# PCIe.net
KiCad netlist of a schematic drawn in Altium Designer
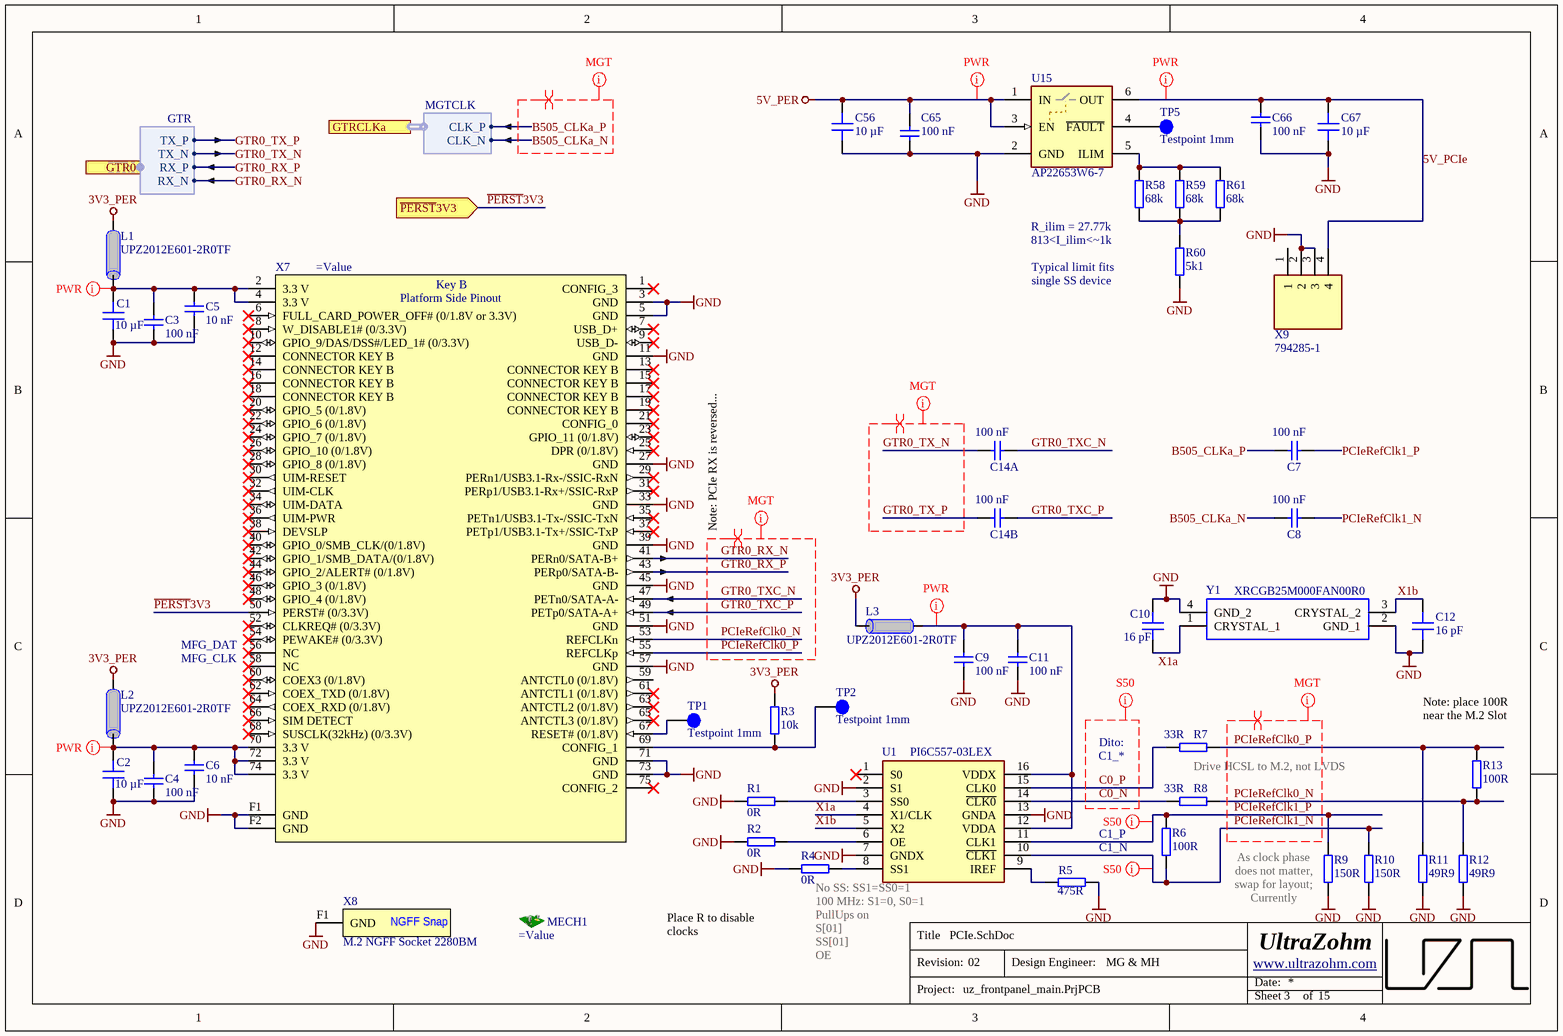
[diagram p0: PCIe.SchDoc]

(export (version "E")
  (design (tool "Eeschema 10.0.6"))
  (components
    (comp (ref "C1")
      (value "10 µF")
      (footprint "C_0603_TE")
      (description "Capacitor 0603, 16 VDC, 10 µF, X5R")
      (fields
        (field (name "MANUFACTURER PART NUMBER") "CL10A106MO8NQNC")
        (field (name "MANUFACTURER") "Samsung Electro-Mechanics")
        (field (name "CREATED FROM") "AGeiger")
      )
      (libsource (lib "user") (part "Capacitor"))
    )
    (comp (ref "C2")
      (value "10 µF")
      (footprint "C_0603_TE")
      (description "Capacitor 0603, 16 VDC, 10 µF, X5R")
      (fields
        (field (name "MANUFACTURER PART NUMBER") "CL10A106MO8NQNC")
        (field (name "MANUFACTURER") "Samsung Electro-Mechanics")
        (field (name "CREATED FROM") "AGeiger")
      )
      (libsource (lib "user") (part "Capacitor"))
    )
    (comp (ref "C3")
      (value "100 nF")
      (footprint "C_0603_TE")
      (description "Generic capacitor")
      (fields
        (field (name "MANUFACTURER PART NUMBER") "UZgen_C_0603_100nF_50V_X7R")
        (field (name "MANUFACTURER") "UZgen")
        (field (name "CREATED FROM") "AGeiger")
      )
      (libsource (lib "user") (part "CAP-NP"))
    )
    (comp (ref "C4")
      (value "100 nF")
      (footprint "C_0603_TE")
      (description "Generic capacitor")
      (fields
        (field (name "MANUFACTURER PART NUMBER") "UZgen_C_0603_100nF_50V_X7R")
        (field (name "MANUFACTURER") "UZgen")
        (field (name "CREATED FROM") "AGeiger")
      )
      (libsource (lib "user") (part "CAP-NP"))
    )
    (comp (ref "C5")
      (value "10 nF")
      (footprint "C_0603_TE")
      (description "Generic capacitor")
      (fields
        (field (name "MANUFACTURER PART NUMBER") "UZgen_C_0603_10nF_50V_X7R")
        (field (name "MANUFACTURER") "UZgen")
        (field (name "CREATED FROM") "UZgenTool")
      )
      (libsource (lib "user") (part "CAP-NP"))
    )
    (comp (ref "C6")
      (value "10 nF")
      (footprint "C_0603_TE")
      (description "Generic capacitor")
      (fields
        (field (name "MANUFACTURER PART NUMBER") "UZgen_C_0603_10nF_50V_X7R")
        (field (name "MANUFACTURER") "UZgen")
        (field (name "CREATED FROM") "UZgenTool")
      )
      (libsource (lib "user") (part "CAP-NP"))
    )
    (comp (ref "C7")
      (value "100 nF")
      (footprint "C_0402_TE")
      (description "Generic capacitor")
      (fields
        (field (name "MANUFACTURER PART NUMBER") "UZgen_C_0402_100nF_50V_X7R")
        (field (name "MANUFACTURER") "UZgen")
        (field (name "CREATED FROM") "UZgenTool")
      )
      (libsource (lib "user") (part "CAP-NP"))
    )
    (comp (ref "C8")
      (value "100 nF")
      (footprint "C_0402_TE")
      (description "Generic capacitor")
      (fields
        (field (name "MANUFACTURER PART NUMBER") "UZgen_C_0402_100nF_50V_X7R")
        (field (name "MANUFACTURER") "UZgen")
        (field (name "CREATED FROM") "UZgenTool")
      )
      (libsource (lib "user") (part "CAP-NP"))
    )
    (comp (ref "C9")
      (value "100 nF")
      (footprint "C_0603_TE")
      (description "Generic capacitor")
      (fields
        (field (name "MANUFACTURER PART NUMBER") "UZgen_C_0603_100nF_50V_X7R")
        (field (name "MANUFACTURER") "UZgen")
        (field (name "CREATED FROM") "AGeiger")
      )
      (libsource (lib "user") (part "CAP-NP"))
    )
    (comp (ref "C10")
      (value "16 pF")
      (footprint "C_0603_TE")
      (description "50V 16pF C0G ±5% 0603 Multilayer Ceramic Capacitors MLCC - SMD/SMT ROHS")
      (fields
        (field (name "TOLERANCE") "5%")
        (field (name "MANUFACTURER PART NUMBER") "0603CG160J500NT")
        (field (name "CREATED FROM") "AGeiger")
      )
      (libsource (lib "user") (part "Capacitor"))
    )
    (comp (ref "C11")
      (value "100 nF")
      (footprint "C_0603_TE")
      (description "Generic capacitor")
      (fields
        (field (name "MANUFACTURER PART NUMBER") "UZgen_C_0603_100nF_50V_X7R")
        (field (name "MANUFACTURER") "UZgen")
        (field (name "CREATED FROM") "AGeiger")
      )
      (libsource (lib "user") (part "CAP-NP"))
    )
    (comp (ref "C12")
      (value "16 pF")
      (footprint "C_0603_TE")
      (description "50V 16pF C0G ±5% 0603 Multilayer Ceramic Capacitors MLCC - SMD/SMT ROHS")
      (fields
        (field (name "TOLERANCE") "5%")
        (field (name "MANUFACTURER PART NUMBER") "0603CG160J500NT")
        (field (name "CREATED FROM") "AGeiger")
      )
      (libsource (lib "user") (part "Capacitor"))
    )
    (comp (ref "C14A")
      (value "100 nF")
      (footprint "C_0402_TE")
      (description "Generic capacitor")
      (fields
        (field (name "MANUFACTURER PART NUMBER") "UZgen_C_0402_100nF_50V_X7R")
        (field (name "MANUFACTURER") "UZgen")
        (field (name "CREATED FROM") "UZgenTool")
      )
      (libsource (lib "user") (part "CAP-NP"))
    )
    (comp (ref "C14B")
      (value "100 nF")
      (footprint "C_0402_TE")
      (description "Generic capacitor")
      (fields
        (field (name "MANUFACTURER PART NUMBER") "UZgen_C_0402_100nF_50V_X7R")
        (field (name "MANUFACTURER") "UZgen")
        (field (name "CREATED FROM") "UZgenTool")
      )
      (libsource (lib "user") (part "CAP-NP"))
    )
    (comp (ref "C56")
      (value "10 µF")
      (footprint "C_0603_TE")
      (description "Capacitor 0603, 16 VDC, 10 µF, X5R")
      (fields
        (field (name "MANUFACTURER PART NUMBER") "CL10A106MO8NQNC")
        (field (name "MANUFACTURER") "Samsung Electro-Mechanics")
        (field (name "CREATED FROM") "AGeiger")
      )
      (libsource (lib "user") (part "Capacitor"))
    )
    (comp (ref "C65")
      (value "100 nF")
      (footprint "C_0603_TE")
      (description "Generic capacitor")
      (fields
        (field (name "MANUFACTURER PART NUMBER") "UZgen_C_0603_100nF_50V_X7R")
        (field (name "MANUFACTURER") "UZgen")
        (field (name "CREATED FROM") "AGeiger")
      )
      (libsource (lib "user") (part "CAP-NP"))
    )
    (comp (ref "C66")
      (value "100 nF")
      (footprint "C_0603_TE")
      (description "Generic capacitor")
      (fields
        (field (name "MANUFACTURER PART NUMBER") "UZgen_C_0603_100nF_50V_X7R")
        (field (name "MANUFACTURER") "UZgen")
        (field (name "CREATED FROM") "AGeiger")
      )
      (libsource (lib "user") (part "CAP-NP"))
    )
    (comp (ref "C67")
      (value "10 µF")
      (footprint "C_0603_TE")
      (description "Capacitor 0603, 16 VDC, 10 µF, X5R")
      (fields
        (field (name "MANUFACTURER PART NUMBER") "CL10A106MO8NQNC")
        (field (name "MANUFACTURER") "Samsung Electro-Mechanics")
        (field (name "CREATED FROM") "AGeiger")
      )
      (libsource (lib "user") (part "Capacitor"))
    )
    (comp (ref "L1")
      (value "UPZ2012E601-2R0TF")
      (footprint "INDC2012X92N_V")
      (description "2A 1 90mΩ 600Ω@100MHz ±25% 0805  Ferrite Beads ROHS")
      (fields
        (field (name "MANUFACTURER") "Sunlord")
        (field (name "LCSC PART NUMBER") "C98308")
        (field (name "CREATED FROM") "AGeiger")
      )
      (libsource (lib "") (part "Ferrite_Bead_1"))
    )
    (comp (ref "L2")
      (value "UPZ2012E601-2R0TF")
      (footprint "INDC2012X92N_V")
      (description "2A 1 90mΩ 600Ω@100MHz ±25% 0805  Ferrite Beads ROHS")
      (fields
        (field (name "MANUFACTURER") "Sunlord")
        (field (name "LCSC PART NUMBER") "C98308")
        (field (name "CREATED FROM") "AGeiger")
      )
      (libsource (lib "") (part "Ferrite_Bead_1"))
    )
    (comp (ref "L3")
      (value "UPZ2012E601-2R0TF")
      (footprint "INDC2012X92N_V")
      (description "2A 1 90mΩ 600Ω@100MHz ±25% 0805  Ferrite Beads ROHS")
      (fields
        (field (name "MANUFACTURER") "Sunlord")
        (field (name "LCSC PART NUMBER") "C98308")
        (field (name "CREATED FROM") "AGeiger")
      )
      (libsource (lib "user") (part "Ferrite_Bead"))
    )
    (comp (ref "MECH1")
      (value "~")
      (footprint "WA-SMSI-2.5mm")
      (description "SMD Nut")
      (fields
        (field (name "LCSC PART #") "C5301784")
        (field (name "MANUFACTURER PART NUMBER") "SMTSOM325BTR")
        (field (name "CREATED FROM") "AGeiger")
      )
      (libsource (lib "user") (part "SMTSOM325BTR"))
    )
    (comp (ref "R1")
      (value "0R")
      (footprint "R_0603_TE")
      (description "Generic resistor")
      (fields
        (field (name "MANUFACTURER PART NUMBER") "UZgen_R_0603_0R")
        (field (name "MANUFACTURER") "UZgen")
        (field (name "CREATED FROM") "UZgenTool")
      )
      (libsource (lib "user") (part "RES"))
    )
    (comp (ref "R2")
      (value "0R")
      (footprint "R_0603_TE")
      (description "Generic resistor")
      (fields
        (field (name "MANUFACTURER PART NUMBER") "UZgen_R_0603_0R")
        (field (name "MANUFACTURER") "UZgen")
        (field (name "CREATED FROM") "UZgenTool")
      )
      (libsource (lib "user") (part "RES"))
    )
    (comp (ref "R3")
      (value "10k")
      (footprint "R_0603_TE")
      (description "Generic resistor")
      (fields
        (field (name "MANUFACTURER PART NUMBER") "UZgen_R_0603_10k")
        (field (name "MANUFACTURER") "UZgen")
        (field (name "CREATED FROM") "AGeiger")
      )
      (libsource (lib "user") (part "RES"))
    )
    (comp (ref "R4")
      (value "0R")
      (footprint "R_0603_TE")
      (description "Generic resistor")
      (fields
        (field (name "MANUFACTURER PART NUMBER") "UZgen_R_0603_0R")
        (field (name "MANUFACTURER") "UZgen")
        (field (name "CREATED FROM") "UZgenTool")
      )
      (libsource (lib "user") (part "RES"))
    )
    (comp (ref "R5")
      (value "475R")
      (footprint "RES 0603_1608")
      (description "100mW Thick Film Resistors 75V ±100ppm/℃ ±1% 475Ω 0603 Chip Resistor - Surface Mount ROHS")
      (fields
        (field (name "TOLERANCE") "1%")
        (field (name "MANUFACTURER PART NUMBER") "RC0603FR-07475RL")
        (field (name "CREATED FROM") "AGeiger")
      )
      (libsource (lib "user") (part "Resistor"))
    )
    (comp (ref "R6")
      (value "100R")
      (footprint "R_0603_TE")
      (description "Generic resistor")
      (fields
        (field (name "MANUFACTURER PART NUMBER") "UZgen_R_0603_100R")
        (field (name "MANUFACTURER") "UZgen")
        (field (name "CREATED FROM") "UZgenTool")
      )
      (libsource (lib "user") (part "RES"))
    )
    (comp (ref "R7")
      (value "33R")
      (footprint "R_0603_TE")
      (description "Generic resistor")
      (fields
        (field (name "MANUFACTURER PART NUMBER") "UZgen_R_0603_33R")
        (field (name "MANUFACTURER") "UZgen")
        (field (name "CREATED FROM") "UZgenTool")
      )
      (libsource (lib "user") (part "RES"))
    )
    (comp (ref "R8")
      (value "33R")
      (footprint "R_0603_TE")
      (description "Generic resistor")
      (fields
        (field (name "MANUFACTURER PART NUMBER") "UZgen_R_0603_33R")
        (field (name "MANUFACTURER") "UZgen")
        (field (name "CREATED FROM") "UZgenTool")
      )
      (libsource (lib "user") (part "RES"))
    )
    (comp (ref "R9")
      (value "150R")
      (footprint "R_0603_TE")
      (description "Generic resistor")
      (fields
        (field (name "MANUFACTURER PART NUMBER") "UZgen_R_0603_150R")
        (field (name "MANUFACTURER") "UZgen")
        (field (name "CREATED FROM") "UZgenTool")
      )
      (libsource (lib "user") (part "RES"))
    )
    (comp (ref "R10")
      (value "150R")
      (footprint "R_0603_TE")
      (description "Generic resistor")
      (fields
        (field (name "MANUFACTURER PART NUMBER") "UZgen_R_0603_150R")
        (field (name "MANUFACTURER") "UZgen")
        (field (name "CREATED FROM") "UZgenTool")
      )
      (libsource (lib "user") (part "RES"))
    )
    (comp (ref "R11")
      (value "49R9")
      (footprint "RES 0603_1608")
      (description "100mW Thick Film Resistors ±100ppm/℃ ±1% 49.9Ω 0603 Chip Resistor - Surface Mount ROHS")
      (fields
        (field (name "MANUFACTURER PART NUMBER") "RC0603FR-0749R9L")
        (field (name "MANUFACTURER") "YAGEO")
        (field (name "CREATED FROM") "AGeiger")
      )
      (libsource (lib "user") (part "Resistor"))
    )
    (comp (ref "R12")
      (value "49R9")
      (footprint "RES 0603_1608")
      (description "100mW Thick Film Resistors ±100ppm/℃ ±1% 49.9Ω 0603 Chip Resistor - Surface Mount ROHS")
      (fields
        (field (name "MANUFACTURER PART NUMBER") "RC0603FR-0749R9L")
        (field (name "MANUFACTURER") "YAGEO")
        (field (name "CREATED FROM") "AGeiger")
      )
      (libsource (lib "user") (part "Resistor"))
    )
    (comp (ref "R13")
      (value "100R")
      (footprint "R_0603_TE")
      (description "Generic resistor")
      (fields
        (field (name "MANUFACTURER PART NUMBER") "UZgen_R_0603_100R")
        (field (name "MANUFACTURER") "UZgen")
        (field (name "CREATED FROM") "UZgenTool")
      )
      (libsource (lib "user") (part "RES"))
    )
    (comp (ref "R58")
      (value "68k")
      (footprint "R_0603_TE")
      (description "Generic resistor")
      (fields
        (field (name "MANUFACTURER PART NUMBER") "UZgen_R_0603_68k")
        (field (name "MANUFACTURER") "UZgen")
        (field (name "CREATED FROM") "UZgenTool")
      )
      (libsource (lib "user") (part "RES"))
    )
    (comp (ref "R59")
      (value "68k")
      (footprint "R_0603_TE")
      (description "Generic resistor")
      (fields
        (field (name "MANUFACTURER PART NUMBER") "UZgen_R_0603_68k")
        (field (name "MANUFACTURER") "UZgen")
        (field (name "CREATED FROM") "UZgenTool")
      )
      (libsource (lib "user") (part "RES"))
    )
    (comp (ref "R60")
      (value "5k1")
      (footprint "R_0603_TE")
      (description "Generic resistor")
      (fields
        (field (name "MANUFACTURER PART NUMBER") "UZgen_R_0603_5k1")
        (field (name "MANUFACTURER") "UZgen")
        (field (name "CREATED FROM") "UZgenTool")
      )
      (libsource (lib "user") (part "RES"))
    )
    (comp (ref "R61")
      (value "68k")
      (footprint "R_0603_TE")
      (description "Generic resistor")
      (fields
        (field (name "MANUFACTURER PART NUMBER") "UZgen_R_0603_68k")
        (field (name "MANUFACTURER") "UZgen")
        (field (name "CREATED FROM") "UZgenTool")
      )
      (libsource (lib "user") (part "RES"))
    )
    (comp (ref "TP1")
      (value "Testpoint 1mm")
      (footprint "TP_1mm")
      (fields
        (field (name "MANUFACTURER PART NUMBER") "NULL")
        (field (name "CREATED") "2018_06_25_AGeiger")
        (field (name "CREATED FROM") "AGeiger")
      )
      (libsource (lib "user") (part "TP_1mm"))
    )
    (comp (ref "TP2")
      (value "Testpoint 1mm")
      (footprint "TP_1mm")
      (fields
        (field (name "MANUFACTURER PART NUMBER") "NULL")
        (field (name "CREATED") "2018_06_25_AGeiger")
        (field (name "CREATED FROM") "AGeiger")
      )
      (libsource (lib "user") (part "TP_1mm"))
    )
    (comp (ref "TP5")
      (value "Testpoint 1mm")
      (footprint "TP_1mm")
      (fields
        (field (name "MANUFACTURER PART NUMBER") "NULL")
        (field (name "CREATED") "2018_06_25_AGeiger")
        (field (name "CREATED FROM") "AGeiger")
      )
      (libsource (lib "user") (part "TP_1mm"))
    )
    (comp (ref "U1")
      (value "PI6C557-03LEX")
      (footprint "SOP65P640X120-16N")
      (description "200MHz 2 TSSOP-16 Clock Generators / Frequency Synthesizers / PLL ROHS")
      (fields
        (field (name "MANUFACTURER") "Diodes Inc.")
        (field (name "LCSC PART NUMBER") "C500785")
        (field (name "CREATED FROM") "AGeiger")
      )
      (libsource (lib "user") (part "PI6C557-03LEX"))
    )
    (comp (ref "U15")
      (value "AP22653W6-7")
      (footprint "TSOT26-6")
      (description "Precision Adjustable Current-limited Power Switch")
      (fields
        (field (name "MANUFACTURER") "Diodes Incorporated")
        (field (name "LCSC PART NUMBER") "C2158037")
        (field (name "CREATED FROM") "MGeier")
      )
      (libsource (lib "user") (part "AP22653W6-7"))
    )
    (comp (ref "X7")
      (value "~")
      (footprint "2199230-3")
      (description "M.2 0.5mm Surface Mount 67 SMD,P=0.5mm Card Edge Connectors ROHS")
      (fields
        (field (name "LCSC PART #") "C590854")
        (field (name "MANUFACTURER PART NUMBER") "1-2199230-5")
        (field (name "CREATED FROM") "AGeiger")
      )
      (libsource (lib "user") (part "1-2199230-5"))
    )
    (comp (ref "X8")
      (value "M.2 NGFF Socket 2280BM")
      (footprint "M.2-NGFF-Socket-2280BM")
      (description "M.2 NGFF Socket 2280BM Snap")
      (fields (field (name "MANUFACTURER") "n.a.") (field (name "CREATED FROM") "AGeiger"))
      (libsource (lib "user") (part "SNAP_M2_2280"))
    )
    (comp (ref "X9")
      (value "794285-1")
      (footprint "7942851")
      (description "1 5.08mm Tin Phosphor Bronze Direct Insert Plugin,P=5.08mm Wire To Board Connector ROHS")
      (fields
        (field (name "MANUFACTURER") "TE")
        (field (name "LCSC PART NUMBER") "C3743067")
        (field (name "CREATED FROM") "FRosner")
      )
      (libsource (lib "user") (part "794285-1"))
    )
    (comp (ref "Y1")
      (value "XRCGB25M000FAN00R0")
      (footprint "XRCGB25M000FAN00R0")
      (description "25MHz 6pF ±25ppm SMD2016-4P Crystals ROHS")
      (fields
        (field (name "MANUFACTURER") "Murata")
        (field (name "LCSC PART NUMBER") "C1669725")
        (field (name "CREATED FROM") "AGeiger")
      )
      (libsource (lib "user") (part "XRCGB25M000FAN00R0"))
    )
  )
  (nets
    (net (code "3") (name "/5V_PCIe") (class "Default")
      (node (ref "C66") (pin "1") (pinfunction "1_1") (pintype "passive"))
      (node (ref "C67") (pin "2") (pinfunction "2_2") (pintype "passive"))
      (node (ref "U15") (pin "6") (pinfunction "OUT_6") (pintype "power_in"))
      (node (ref "X9") (pin "4") (pinfunction "4_4") (pintype "passive"))
    )
    (net (code "4") (name "/B505_CLKa_N") (class "Default")
      (node (ref "C8") (pin "1") (pinfunction "1_1") (pintype "passive"))
    )
    (net (code "5") (name "/B505_CLKa_P") (class "Default")
      (node (ref "C7") (pin "1") (pinfunction "1_1") (pintype "passive"))
    )
    (net (code "6") (name "/C0_N") (class "Default")
      (node (ref "R8") (pin "1") (pinfunction "1_1") (pintype "passive"))
      (node (ref "U1") (pin "14") (pinfunction "CLK0_14") (pintype "passive"))
    )
    (net (code "7") (name "/C0_P") (class "Default")
      (node (ref "R7") (pin "1") (pinfunction "1_1") (pintype "passive"))
      (node (ref "U1") (pin "15") (pinfunction "CLK0_15") (pintype "passive"))
    )
    (net (code "8") (name "/GTR0_RX_N") (class "Default")
      (node (ref "X7") (pin "41") (pinfunction "PERn0/SATA-B+_41") (pintype "output"))
    )
    (net (code "9") (name "/GTR0_RX_P") (class "Default")
      (node (ref "X7") (pin "43") (pinfunction "PERp0/SATA-B-_43") (pintype "output"))
    )
    (net (code "10") (name "/GTR0_TXC_N") (class "Default")
      (node (ref "C14A") (pin "2") (pinfunction "2_2") (pintype "passive"))
      (node (ref "X7") (pin "47") (pinfunction "PETn0/SATA-A-_47") (pintype "input"))
    )
    (net (code "11") (name "/GTR0_TXC_P") (class "Default")
      (node (ref "C14B") (pin "2") (pinfunction "2_2") (pintype "passive"))
      (node (ref "X7") (pin "49") (pinfunction "PETp0/SATA-A+_49") (pintype "input"))
    )
    (net (code "12") (name "/GTR0_TX_N") (class "Default")
      (node (ref "C14A") (pin "1") (pinfunction "1_1") (pintype "passive"))
    )
    (net (code "13") (name "/GTR0_TX_P") (class "Default")
      (node (ref "C14B") (pin "1") (pinfunction "1_1") (pintype "passive"))
    )
    (net (code "14") (name "/PCIeRefClk0_N") (class "Default")
      (node (ref "R12") (pin "2") (pinfunction "2_2") (pintype "passive"))
      (node (ref "R13") (pin "1") (pinfunction "1_1") (pintype "passive"))
      (node (ref "R8") (pin "2") (pinfunction "2_2") (pintype "passive"))
      (node (ref "X7") (pin "53") (pinfunction "REFCLKn_53") (pintype "input"))
    )
    (net (code "15") (name "/PCIeRefClk0_P") (class "Default")
      (node (ref "R11") (pin "2") (pinfunction "2_2") (pintype "passive"))
      (node (ref "R13") (pin "2") (pinfunction "2_2") (pintype "passive"))
      (node (ref "R7") (pin "2") (pinfunction "2_2") (pintype "passive"))
      (node (ref "X7") (pin "55") (pinfunction "REFCLKp_55") (pintype "input"))
    )
    (net (code "16") (name "/PCIeRefClk1_N") (class "Default")
      (node (ref "C8") (pin "2") (pinfunction "2_2") (pintype "passive"))
      (node (ref "R10") (pin "2") (pinfunction "2_2") (pintype "passive"))
      (node (ref "R6") (pin "1") (pinfunction "1_1") (pintype "passive"))
      (node (ref "U1") (pin "10") (pinfunction "CLK1_10") (pintype "passive"))
    )
    (net (code "17") (name "/PCIeRefClk1_P") (class "Default")
      (node (ref "C7") (pin "2") (pinfunction "2_2") (pintype "passive"))
      (node (ref "R6") (pin "2") (pinfunction "2_2") (pintype "passive"))
      (node (ref "R9") (pin "2") (pinfunction "2_2") (pintype "passive"))
      (node (ref "U1") (pin "11") (pinfunction "CLK1_11") (pintype "passive"))
    )
    (net (code "18") (name "/X1a") (class "Default")
      (node (ref "C10") (pin "2") (pinfunction "2_2") (pintype "passive"))
      (node (ref "U1") (pin "4") (pinfunction "X1/CLK_4") (pintype "passive"))
      (node (ref "Y1") (pin "1") (pinfunction "CRYSTAL_1_1") (pintype "passive"))
    )
    (net (code "19") (name "/X1b") (class "Default")
      (node (ref "C12") (pin "1") (pinfunction "1_1") (pintype "passive"))
      (node (ref "U1") (pin "5") (pinfunction "X2_5") (pintype "passive"))
      (node (ref "Y1") (pin "3") (pinfunction "CRYSTAL_2_3") (pintype "passive"))
    )
    (net (code "22") (name "/~{PERST}3V3") (class "Default")
      (node (ref "X7") (pin "50") (pinfunction "PERST#_(0/3.3V)_50") (pintype "input"))
    )
    (net (code "23") (name "3V3_PER") (class "Default")
      (node (ref "L1") (pin "1") (pinfunction "1_1") (pintype "passive"))
      (node (ref "L2") (pin "1") (pinfunction "1_1") (pintype "passive"))
      (node (ref "L3") (pin "2") (pinfunction "2_2") (pintype "passive"))
      (node (ref "R3") (pin "2") (pinfunction "2_2") (pintype "passive"))
    )
    (net (code "24") (name "5V_PER") (class "Default")
      (node (ref "C56") (pin "2") (pinfunction "2_2") (pintype "passive"))
      (node (ref "C65") (pin "1") (pinfunction "1_1") (pintype "passive"))
      (node (ref "U15") (pin "1") (pinfunction "IN_1") (pintype "power_in"))
      (node (ref "U15") (pin "3") (pinfunction "EN_3") (pintype "input"))
    )
    (net (code "25") (name "GND") (class "Default")
      (node (ref "C1") (pin "1") (pinfunction "1_1") (pintype "passive"))
      (node (ref "C10") (pin "1") (pinfunction "1_1") (pintype "passive"))
      (node (ref "C11") (pin "1") (pinfunction "1_1") (pintype "passive"))
      (node (ref "C12") (pin "2") (pinfunction "2_2") (pintype "passive"))
      (node (ref "C2") (pin "1") (pinfunction "1_1") (pintype "passive"))
      (node (ref "C3") (pin "1") (pinfunction "1_1") (pintype "passive"))
      (node (ref "C4") (pin "1") (pinfunction "1_1") (pintype "passive"))
      (node (ref "C5") (pin "1") (pinfunction "1_1") (pintype "passive"))
      (node (ref "C56") (pin "1") (pinfunction "1_1") (pintype "passive"))
      (node (ref "C6") (pin "1") (pinfunction "1_1") (pintype "passive"))
      (node (ref "C65") (pin "2") (pinfunction "2_2") (pintype "passive"))
      (node (ref "C66") (pin "2") (pinfunction "2_2") (pintype "passive"))
      (node (ref "C67") (pin "1") (pinfunction "1_1") (pintype "passive"))
      (node (ref "C9") (pin "1") (pinfunction "1_1") (pintype "passive"))
      (node (ref "R1") (pin "1") (pinfunction "1_1") (pintype "passive"))
      (node (ref "R10") (pin "1") (pinfunction "1_1") (pintype "passive"))
      (node (ref "R11") (pin "1") (pinfunction "1_1") (pintype "passive"))
      (node (ref "R12") (pin "1") (pinfunction "1_1") (pintype "passive"))
      (node (ref "R2") (pin "1") (pinfunction "1_1") (pintype "passive"))
      (node (ref "R4") (pin "1") (pinfunction "1_1") (pintype "passive"))
      (node (ref "R5") (pin "1") (pinfunction "1_1") (pintype "passive"))
      (node (ref "R60") (pin "1") (pinfunction "1_1") (pintype "passive"))
      (node (ref "R9") (pin "1") (pinfunction "1_1") (pintype "passive"))
      (node (ref "U1") (pin "13") (pinfunction "GNDA_13") (pintype "passive"))
      (node (ref "U1") (pin "2") (pinfunction "S1_2") (pintype "passive"))
      (node (ref "U1") (pin "7") (pinfunction "GNDX_7") (pintype "passive"))
      (node (ref "U15") (pin "2") (pinfunction "GND_2") (pintype "power_in"))
      (node (ref "X7") (pin "11") (pinfunction "GND_11") (pintype "power_in"))
      (node (ref "X7") (pin "27") (pinfunction "GND_27") (pintype "power_in"))
      (node (ref "X7") (pin "3") (pinfunction "GND_3") (pintype "power_in"))
      (node (ref "X7") (pin "33") (pinfunction "GND_33") (pintype "power_in"))
      (node (ref "X7") (pin "39") (pinfunction "GND_39") (pintype "power_in"))
      (node (ref "X7") (pin "45") (pinfunction "GND_45") (pintype "power_in"))
      (node (ref "X7") (pin "5") (pinfunction "GND_5") (pintype "power_in"))
      (node (ref "X7") (pin "51") (pinfunction "GND_51") (pintype "power_in"))
      (node (ref "X7") (pin "57") (pinfunction "GND_57") (pintype "power_in"))
      (node (ref "X7") (pin "71") (pinfunction "GND_71") (pintype "power_in"))
      (node (ref "X7") (pin "73") (pinfunction "GND_73") (pintype "power_in"))
      (node (ref "X7") (pin "F1") (pinfunction "GND_F1") (pintype "power_in"))
      (node (ref "X7") (pin "F2") (pinfunction "GND_F2") (pintype "power_in"))
      (node (ref "X8") (pin "F1") (pinfunction "GND_F1") (pintype "passive"))
      (node (ref "X9") (pin "2") (pinfunction "2_2") (pintype "passive"))
      (node (ref "X9") (pin "3") (pinfunction "3_3") (pintype "passive"))
      (node (ref "Y1") (pin "2") (pinfunction "GND_1_2") (pintype "passive"))
      (node (ref "Y1") (pin "4") (pinfunction "GND_2_4") (pintype "passive"))
    )
    (net (code "26") (name "Net-(C1-Pad2)") (class "Default")
      (node (ref "C1") (pin "2") (pinfunction "2_2") (pintype "passive"))
      (node (ref "C3") (pin "2") (pinfunction "2_2") (pintype "passive"))
      (node (ref "C5") (pin "2") (pinfunction "2_2") (pintype "passive"))
      (node (ref "L1") (pin "2") (pinfunction "2_2") (pintype "passive"))
      (node (ref "X7") (pin "2") (pinfunction "3.3_V_2") (pintype "power_in"))
      (node (ref "X7") (pin "4") (pinfunction "3.3_V_4") (pintype "power_in"))
    )
    (net (code "27") (name "Net-(C2-Pad2)") (class "Default")
      (node (ref "C2") (pin "2") (pinfunction "2_2") (pintype "passive"))
      (node (ref "C4") (pin "2") (pinfunction "2_2") (pintype "passive"))
      (node (ref "C6") (pin "2") (pinfunction "2_2") (pintype "passive"))
      (node (ref "L2") (pin "2") (pinfunction "2_2") (pintype "passive"))
      (node (ref "X7") (pin "70") (pinfunction "3.3_V_70") (pintype "power_in"))
      (node (ref "X7") (pin "72") (pinfunction "3.3_V_72") (pintype "power_in"))
      (node (ref "X7") (pin "74") (pinfunction "3.3_V_74") (pintype "power_in"))
    )
    (net (code "28") (name "Net-(R58-Pad1)") (class "Default")
      (node (ref "R58") (pin "1") (pinfunction "1_1") (pintype "passive"))
      (node (ref "R59") (pin "1") (pinfunction "1_1") (pintype "passive"))
      (node (ref "R60") (pin "2") (pinfunction "2_2") (pintype "passive"))
      (node (ref "R61") (pin "1") (pinfunction "1_1") (pintype "passive"))
    )
    (net (code "29") (name "Net-(U1-IREF)") (class "Default")
      (node (ref "R5") (pin "2") (pinfunction "2_2") (pintype "passive"))
      (node (ref "U1") (pin "9") (pinfunction "IREF_9") (pintype "passive"))
    )
    (net (code "30") (name "Net-(U1-OE)") (class "Default")
      (node (ref "R2") (pin "2") (pinfunction "2_2") (pintype "passive"))
      (node (ref "U1") (pin "6") (pinfunction "OE_6") (pintype "passive"))
    )
    (net (code "31") (name "Net-(U1-SS0)") (class "Default")
      (node (ref "R1") (pin "2") (pinfunction "2_2") (pintype "passive"))
      (node (ref "U1") (pin "3") (pinfunction "SS0_3") (pintype "passive"))
    )
    (net (code "32") (name "Net-(U1-SS1)") (class "Default")
      (node (ref "R4") (pin "2") (pinfunction "2_2") (pintype "passive"))
      (node (ref "U1") (pin "8") (pinfunction "SS1_8") (pintype "passive"))
    )
    (net (code "33") (name "Net-(U1-VDDA)") (class "Default")
      (node (ref "C11") (pin "2") (pinfunction "2_2") (pintype "passive"))
      (node (ref "C9") (pin "2") (pinfunction "2_2") (pintype "passive"))
      (node (ref "L3") (pin "1") (pinfunction "1_1") (pintype "passive"))
      (node (ref "U1") (pin "12") (pinfunction "VDDA_12") (pintype "passive"))
      (node (ref "U1") (pin "16") (pinfunction "VDDX_16") (pintype "passive"))
    )
    (net (code "34") (name "Net-(U15-ILIM)") (class "Default")
      (node (ref "R58") (pin "2") (pinfunction "2_2") (pintype "passive"))
      (node (ref "R59") (pin "2") (pinfunction "2_2") (pintype "passive"))
      (node (ref "R61") (pin "2") (pinfunction "2_2") (pintype "passive"))
      (node (ref "U15") (pin "5") (pinfunction "ILIM_5") (pintype "passive"))
    )
    (net (code "35") (name "Net-(U15-~{FAULT})") (class "Default")
      (node (ref "TP5") (pin "1") (pintype "passive"))
      (node (ref "U15") (pin "4") (pinfunction "~{FAULT}_4") (pintype "open_collector"))
    )
    (net (code "36") (name "Net-(X7-CONFIG_1)") (class "Default")
      (node (ref "R3") (pin "1") (pinfunction "1_1") (pintype "passive"))
      (node (ref "TP2") (pin "1") (pintype "passive"))
      (node (ref "X7") (pin "69") (pinfunction "CONFIG_1_69") (pintype "passive"))
    )
    (net (code "37") (name "Net-(X7-RESET#_(0{slash}1.8V))") (class "Default")
      (node (ref "TP1") (pin "1") (pintype "passive"))
      (node (ref "X7") (pin "67") (pinfunction "RESET#_(0/1.8V)_67") (pintype "input"))
    )
    (net (code "38") (name "unconnected-(U1-S0-Pad1)") (class "Default")
      (node (ref "U1") (pin "1") (pinfunction "S0_1") (pintype "passive+no_connect"))
    )
    (net (code "39") (name "unconnected-(X7-ANTCTL0_(0{slash}1.8V)-Pad59)") (class "Default")
      (node (ref "X7") (pin "59") (pinfunction "ANTCTL0_(0/1.8V)_59") (pintype "output"))
    )
    (net (code "40") (name "unconnected-(X7-ANTCTL1_(0{slash}1.8V)-Pad61)") (class "Default")
      (node (ref "X7") (pin "61") (pinfunction "ANTCTL1_(0/1.8V)_61") (pintype "output+no_connect"))
    )
    (net (code "41") (name "unconnected-(X7-ANTCTL2_(0{slash}1.8V)-Pad63)") (class "Default")
      (node (ref "X7") (pin "63") (pinfunction "ANTCTL2_(0/1.8V)_63") (pintype "output+no_connect"))
    )
    (net (code "42") (name "unconnected-(X7-ANTCTL3_(0{slash}1.8V)-Pad65)") (class "Default")
      (node (ref "X7") (pin "65") (pinfunction "ANTCTL3_(0/1.8V)_65") (pintype "output+no_connect"))
    )
    (net (code "43") (name "unconnected-(X7-CLKREQ#_(0{slash}3.3V)-Pad52)") (class "Default")
      (node (ref "X7") (pin "52") (pinfunction "CLKREQ#_(0/3.3V)_52") (pintype "bidirectional+no_connect"))
    )
    (net (code "44") (name "unconnected-(X7-COEX3_(0{slash}1.8V)-Pad60)") (class "Default")
      (node (ref "X7") (pin "60") (pinfunction "COEX3_(0/1.8V)_60") (pintype "bidirectional+no_connect"))
    )
    (net (code "45") (name "unconnected-(X7-COEX_RXD_(0{slash}1.8V)-Pad64)") (class "Default")
      (node (ref "X7") (pin "64") (pinfunction "COEX_RXD_(0/1.8V)_64") (pintype "output+no_connect"))
    )
    (net (code "46") (name "unconnected-(X7-COEX_TXD_(0{slash}1.8V)-Pad62)") (class "Default")
      (node (ref "X7") (pin "62") (pinfunction "COEX_TXD_(0/1.8V)_62") (pintype "input+no_connect"))
    )
    (net (code "47") (name "unconnected-(X7-CONFIG_0-Pad21)") (class "Default")
      (node (ref "X7") (pin "21") (pinfunction "CONFIG_0_21") (pintype "passive+no_connect"))
    )
    (net (code "48") (name "unconnected-(X7-CONFIG_2-Pad75)") (class "Default")
      (node (ref "X7") (pin "75") (pinfunction "CONFIG_2_75") (pintype "passive+no_connect"))
    )
    (net (code "49") (name "unconnected-(X7-CONFIG_3-Pad1)") (class "Default")
      (node (ref "X7") (pin "1") (pinfunction "CONFIG_3_1") (pintype "passive+no_connect"))
    )
    (net (code "50") (name "unconnected-(X7-CONNECTOR_KEY_B-Pad12)") (class "Default")
      (node (ref "X7") (pin "12") (pinfunction "CONNECTOR_KEY_B_12") (pintype "passive+no_connect"))
    )
    (net (code "51") (name "unconnected-(X7-CONNECTOR_KEY_B-Pad13)") (class "Default")
      (node (ref "X7") (pin "13") (pinfunction "CONNECTOR_KEY_B_13") (pintype "passive+no_connect"))
    )
    (net (code "52") (name "unconnected-(X7-CONNECTOR_KEY_B-Pad14)") (class "Default")
      (node (ref "X7") (pin "14") (pinfunction "CONNECTOR_KEY_B_14") (pintype "passive+no_connect"))
    )
    (net (code "53") (name "unconnected-(X7-CONNECTOR_KEY_B-Pad15)") (class "Default")
      (node (ref "X7") (pin "15") (pinfunction "CONNECTOR_KEY_B_15") (pintype "passive+no_connect"))
    )
    (net (code "54") (name "unconnected-(X7-CONNECTOR_KEY_B-Pad16)") (class "Default")
      (node (ref "X7") (pin "16") (pinfunction "CONNECTOR_KEY_B_16") (pintype "passive+no_connect"))
    )
    (net (code "55") (name "unconnected-(X7-CONNECTOR_KEY_B-Pad17)") (class "Default")
      (node (ref "X7") (pin "17") (pinfunction "CONNECTOR_KEY_B_17") (pintype "passive+no_connect"))
    )
    (net (code "56") (name "unconnected-(X7-CONNECTOR_KEY_B-Pad18)") (class "Default")
      (node (ref "X7") (pin "18") (pinfunction "CONNECTOR_KEY_B_18") (pintype "passive+no_connect"))
    )
    (net (code "57") (name "unconnected-(X7-CONNECTOR_KEY_B-Pad19)") (class "Default")
      (node (ref "X7") (pin "19") (pinfunction "CONNECTOR_KEY_B_19") (pintype "passive+no_connect"))
    )
    (net (code "58") (name "unconnected-(X7-DEVSLP-Pad38)") (class "Default")
      (node (ref "X7") (pin "38") (pinfunction "DEVSLP_38") (pintype "input+no_connect"))
    )
    (net (code "59") (name "unconnected-(X7-DPR_(0{slash}1.8V)-Pad25)") (class "Default")
      (node (ref "X7") (pin "25") (pinfunction "DPR_(0/1.8V)_25") (pintype "input+no_connect"))
    )
    (net (code "60") (name "unconnected-(X7-FULL_CARD_POWER_OFF#_(0{slash}1.8V_or_3.3V)-Pad6)") (class "Default")
      (node (ref "X7") (pin "6") (pinfunction "FULL_CARD_POWER_OFF#_(0/1.8V_or_3.3V)_6") (pintype "input+no_connect"))
    )
    (net (code "61") (name "unconnected-(X7-GPIO_0{slash}SMB_CLK{slash}(0{slash}1.8V)-Pad40)") (class "Default")
      (node (ref "X7") (pin "40") (pinfunction "GPIO_0/SMB_CLK/(0/1.8V)_40") (pintype "bidirectional+no_connect"))
    )
    (net (code "62") (name "unconnected-(X7-GPIO_1{slash}SMB_DATA{slash}(0{slash}1.8V)-Pad42)") (class "Default")
      (node (ref "X7") (pin "42") (pinfunction "GPIO_1/SMB_DATA/(0/1.8V)_42") (pintype "bidirectional+no_connect"))
    )
    (net (code "63") (name "unconnected-(X7-GPIO_2{slash}ALERT#_(0{slash}1.8V)-Pad44)") (class "Default")
      (node (ref "X7") (pin "44") (pinfunction "GPIO_2/ALERT#_(0/1.8V)_44") (pintype "bidirectional+no_connect"))
    )
    (net (code "64") (name "unconnected-(X7-GPIO_3_(0{slash}1.8V)-Pad46)") (class "Default")
      (node (ref "X7") (pin "46") (pinfunction "GPIO_3_(0/1.8V)_46") (pintype "bidirectional+no_connect"))
    )
    (net (code "65") (name "unconnected-(X7-GPIO_4_(0{slash}1.8V)-Pad48)") (class "Default")
      (node (ref "X7") (pin "48") (pinfunction "GPIO_4_(0/1.8V)_48") (pintype "bidirectional+no_connect"))
    )
    (net (code "66") (name "unconnected-(X7-GPIO_5_(0{slash}1.8V)-Pad20)") (class "Default")
      (node (ref "X7") (pin "20") (pinfunction "GPIO_5_(0/1.8V)_20") (pintype "bidirectional+no_connect"))
    )
    (net (code "67") (name "unconnected-(X7-GPIO_6_(0{slash}1.8V)-Pad22)") (class "Default")
      (node (ref "X7") (pin "22") (pinfunction "GPIO_6_(0/1.8V)_22") (pintype "bidirectional+no_connect"))
    )
    (net (code "68") (name "unconnected-(X7-GPIO_7_(0{slash}1.8V)-Pad24)") (class "Default")
      (node (ref "X7") (pin "24") (pinfunction "GPIO_7_(0/1.8V)_24") (pintype "bidirectional+no_connect"))
    )
    (net (code "69") (name "unconnected-(X7-GPIO_8_(0{slash}1.8V)-Pad28)") (class "Default")
      (node (ref "X7") (pin "28") (pinfunction "GPIO_8_(0/1.8V)_28") (pintype "bidirectional+no_connect"))
    )
    (net (code "70") (name "unconnected-(X7-GPIO_9{slash}DAS{slash}DSS#{slash}LED_1#_(0{slash}3.3V)-Pad10)") (class "Default")
      (node (ref "X7") (pin "10") (pinfunction "GPIO_9/DAS/DSS#/LED_1#_(0/3.3V)_10") (pintype "bidirectional+no_connect"))
    )
    (net (code "71") (name "unconnected-(X7-GPIO_10_(0{slash}1.8V)-Pad26)") (class "Default")
      (node (ref "X7") (pin "26") (pinfunction "GPIO_10_(0/1.8V)_26") (pintype "bidirectional+no_connect"))
    )
    (net (code "72") (name "unconnected-(X7-GPIO_11_(0{slash}1.8V)-Pad23)") (class "Default")
      (node (ref "X7") (pin "23") (pinfunction "GPIO_11_(0/1.8V)_23") (pintype "bidirectional+no_connect"))
    )
    (net (code "73") (name "unconnected-(X7-NC-Pad56)") (class "Default")
      (node (ref "X7") (pin "56") (pinfunction "NC_56") (pintype "passive+no_connect"))
    )
    (net (code "74") (name "unconnected-(X7-NC-Pad58)") (class "Default")
      (node (ref "X7") (pin "58") (pinfunction "NC_58") (pintype "passive+no_connect"))
    )
    (net (code "75") (name "unconnected-(X7-PERn1{slash}USB3.1-Rx-{slash}SSIC-RxN-Pad29)") (class "Default")
      (node (ref "X7") (pin "29") (pinfunction "PERn1/USB3.1-Rx-/SSIC-RxN_29") (pintype "output+no_connect"))
    )
    (net (code "76") (name "unconnected-(X7-PERp1{slash}USB3.1-Rx+{slash}SSIC-RxP-Pad31)") (class "Default")
      (node (ref "X7") (pin "31") (pinfunction "PERp1/USB3.1-Rx+/SSIC-RxP_31") (pintype "output+no_connect"))
    )
    (net (code "77") (name "unconnected-(X7-PETn1{slash}USB3.1-Tx-{slash}SSIC-TxN-Pad35)") (class "Default")
      (node (ref "X7") (pin "35") (pinfunction "PETn1/USB3.1-Tx-/SSIC-TxN_35") (pintype "input+no_connect"))
    )
    (net (code "78") (name "unconnected-(X7-PETp1{slash}USB3.1-Tx+{slash}SSIC-TxP-Pad37)") (class "Default")
      (node (ref "X7") (pin "37") (pinfunction "PETp1/USB3.1-Tx+/SSIC-TxP_37") (pintype "input+no_connect"))
    )
    (net (code "79") (name "unconnected-(X7-PEWAKE#_(0{slash}3.3V)-Pad54)") (class "Default")
      (node (ref "X7") (pin "54") (pinfunction "PEWAKE#_(0/3.3V)_54") (pintype "bidirectional+no_connect"))
    )
    (net (code "80") (name "unconnected-(X7-SIM_DETECT-Pad66)") (class "Default")
      (node (ref "X7") (pin "66") (pinfunction "SIM_DETECT_66") (pintype "input+no_connect"))
    )
    (net (code "81") (name "unconnected-(X7-SUSCLK(32kHz)_(0{slash}3.3V)-Pad68)") (class "Default")
      (node (ref "X7") (pin "68") (pinfunction "SUSCLK(32kHz)_(0/3.3V)_68") (pintype "input+no_connect"))
    )
    (net (code "82") (name "unconnected-(X7-UIM-CLK-Pad32)") (class "Default")
      (node (ref "X7") (pin "32") (pinfunction "UIM-CLK_32") (pintype "output+no_connect"))
    )
    (net (code "83") (name "unconnected-(X7-UIM-DATA-Pad34)") (class "Default")
      (node (ref "X7") (pin "34") (pinfunction "UIM-DATA_34") (pintype "bidirectional+no_connect"))
    )
    (net (code "84") (name "unconnected-(X7-UIM-PWR-Pad36)") (class "Default")
      (node (ref "X7") (pin "36") (pinfunction "UIM-PWR_36") (pintype "output+no_connect"))
    )
    (net (code "85") (name "unconnected-(X7-UIM-RESET-Pad30)") (class "Default")
      (node (ref "X7") (pin "30") (pinfunction "UIM-RESET_30") (pintype "output+no_connect"))
    )
    (net (code "86") (name "unconnected-(X7-USB_D+-Pad7)") (class "Default")
      (node (ref "X7") (pin "7") (pinfunction "USB_D+_7") (pintype "bidirectional+no_connect"))
    )
    (net (code "87") (name "unconnected-(X7-USB_D--Pad9)") (class "Default")
      (node (ref "X7") (pin "9") (pinfunction "USB_D-_9") (pintype "bidirectional+no_connect"))
    )
    (net (code "88") (name "unconnected-(X7-W_DISABLE1#_(0{slash}3.3V)-Pad8)") (class "Default")
      (node (ref "X7") (pin "8") (pinfunction "W_DISABLE1#_(0/3.3V)_8") (pintype "input+no_connect"))
    )
    (net (code "89") (name "unconnected-(X9-Pad1)") (class "Default")
      (node (ref "X9") (pin "1") (pinfunction "1_1") (pintype "passive"))
    )
  )
)
